# Stereo_Deck.net
KiCad netlist of a schematic drawn in EAGLE
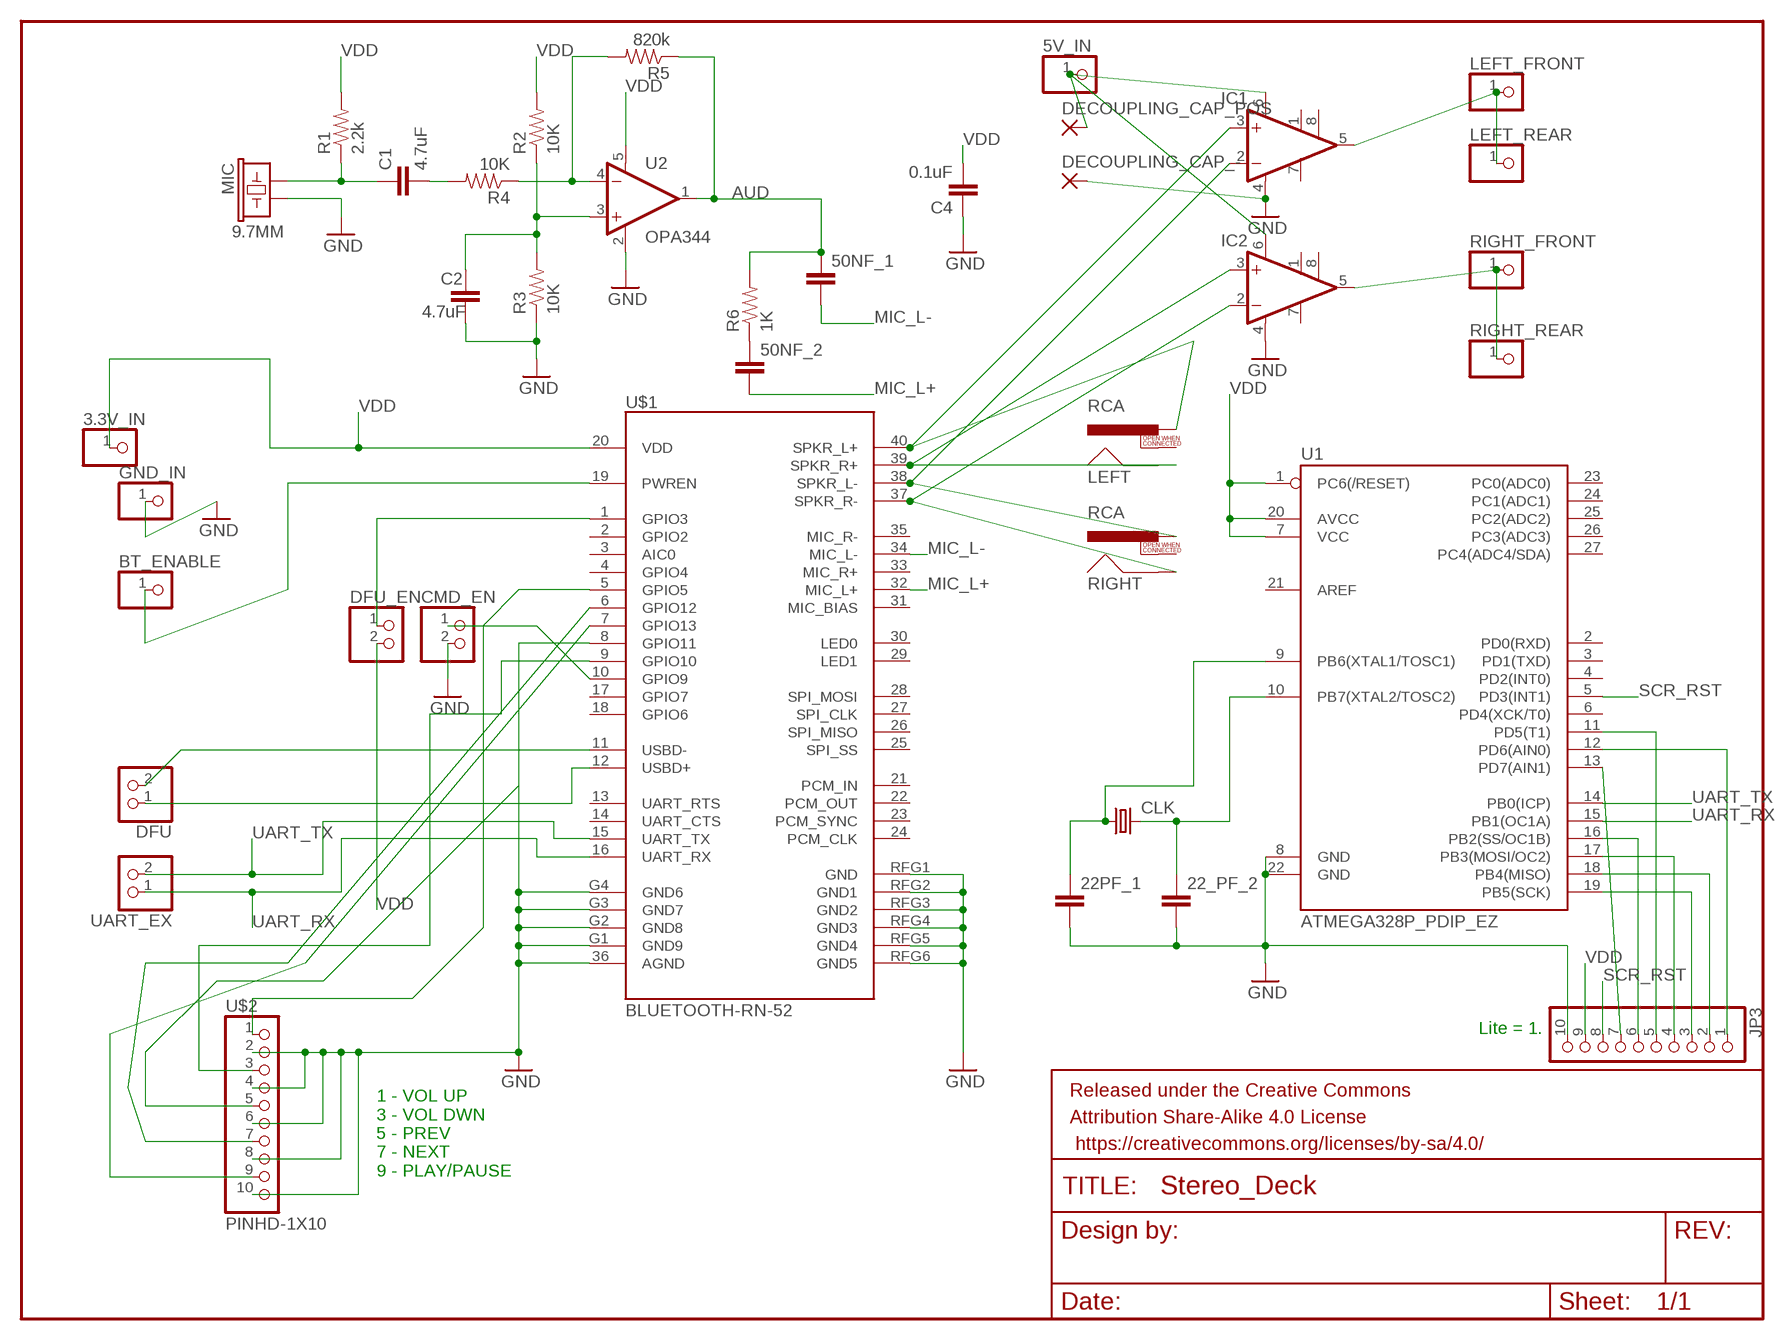
[diagram p0: schematic, sheet 1]

(export (version "E")
  (design (tool "Eeschema 10.0.6"))
  (components
    (comp (ref "3.3V_IN")
      (value "PINHD-1X1")
      (footprint "eagle-import:1X01")
      (libsource (lib "eagle-import") (part "PINHD-1X1"))
    )
    (comp (ref "5V_IN")
      (value "PINHD-1X1")
      (footprint "eagle-import:1X01")
      (libsource (lib "eagle-import") (part "PINHD-1X1"))
    )
    (comp (ref "22PF_1")
      (value "CC0603")
      (footprint "eagle-import:C0603")
      (libsource (lib "eagle-import") (part "CC0603"))
    )
    (comp (ref "22_PF_2")
      (value "CC0603")
      (footprint "eagle-import:C0603")
      (libsource (lib "eagle-import") (part "CC0603"))
    )
    (comp (ref "50NF_1")
      (value "CC0603")
      (footprint "eagle-import:C0603")
      (libsource (lib "eagle-import") (part "CC0603"))
    )
    (comp (ref "50NF_2")
      (value "CC0603")
      (footprint "eagle-import:C0603")
      (libsource (lib "eagle-import") (part "CC0603"))
    )
    (comp (ref "BT_ENABLE")
      (value "PINHD-1X1")
      (footprint "eagle-import:1X01")
      (libsource (lib "eagle-import") (part "PINHD-1X1"))
    )
    (comp (ref "C1")
      (value "4.7uF")
      (footprint "eagle-import:0603-CAP")
      (libsource (lib "eagle-import") (part "4.7UF-6.3V-10%(0603)0603"))
    )
    (comp (ref "C2")
      (value "4.7uF")
      (footprint "eagle-import:0603-CAP")
      (libsource (lib "eagle-import") (part "4.7UF-6.3V-10%(0603)0603"))
    )
    (comp (ref "C4")
      (value "0.1uF")
      (footprint "eagle-import:0603-CAP")
      (libsource (lib "eagle-import") (part "0.1UF-25V(+80/-20%)(0603)"))
    )
    (comp (ref "CLK")
      (value "CRYSTALHC49US")
      (footprint "eagle-import:HC49US")
      (libsource (lib "eagle-import") (part "CRYSTALHC49US"))
    )
    (comp (ref "CMD_EN")
      (value "PINHD-1X2")
      (footprint "eagle-import:1X02")
      (libsource (lib "eagle-import") (part "PINHD-1X2"))
    )
    (comp (ref "DECOUPLING_CAP_-")
      (value "2,15/1,0")
      (footprint "eagle-import:2,15_1,0")
      (libsource (lib "eagle-import") (part "2,15/1,0"))
    )
    (comp (ref "DECOUPLING_CAP_POS")
      (value "2,15/1,0")
      (footprint "eagle-import:2,15_1,0")
      (libsource (lib "eagle-import") (part "2,15/1,0"))
    )
    (comp (ref "DFU")
      (value "PINHD-1X2")
      (footprint "eagle-import:1X02")
      (libsource (lib "eagle-import") (part "PINHD-1X2"))
    )
    (comp (ref "DFU_EN")
      (value "PINHD-1X2")
      (footprint "eagle-import:1X02")
      (libsource (lib "eagle-import") (part "PINHD-1X2"))
    )
    (comp (ref "FRAME1")
      (value "FRAME-LETTER")
      (footprint "eagle-import:CREATIVE_COMMONS")
      (libsource (lib "eagle-import") (part "FRAME-LETTER"))
    )
    (comp (ref "GND_IN")
      (value "PINHD-1X1")
      (footprint "eagle-import:1X01")
      (libsource (lib "eagle-import") (part "PINHD-1X1"))
    )
    (comp (ref "IC1")
      (value "LM386N-1")
      (footprint "eagle-import:DIL08")
      (libsource (lib "eagle-import") (part "LM386?-N1"))
    )
    (comp (ref "IC2")
      (value "LM386N-1")
      (footprint "eagle-import:DIL08")
      (libsource (lib "eagle-import") (part "LM386?-N1"))
    )
    (comp (ref "JP3")
      (value "PINHD-1X10")
      (footprint "eagle-import:1X10")
      (libsource (lib "eagle-import") (part "pinhead_PINHD-1X10"))
    )
    (comp (ref "LEFT")
      (value "RCA")
      (footprint "eagle-import:RCA")
      (libsource (lib "eagle-import") (part "RCA"))
    )
    (comp (ref "LEFT_FRONT")
      (value "PINHD-1X1")
      (footprint "eagle-import:1X01")
      (libsource (lib "eagle-import") (part "PINHD-1X1"))
    )
    (comp (ref "LEFT_REAR")
      (value "PINHD-1X1")
      (footprint "eagle-import:1X01")
      (libsource (lib "eagle-import") (part "PINHD-1X1"))
    )
    (comp (ref "MIC")
      (value "9.7MM")
      (footprint "eagle-import:MIC-9.7MM")
      (libsource (lib "eagle-import") (part "MIC9.7MM"))
    )
    (comp (ref "R1")
      (value "2.2k")
      (footprint "eagle-import:0603-RES")
      (libsource (lib "eagle-import") (part "2.2KOHM-1/10W-1%(0603)"))
    )
    (comp (ref "R2")
      (value "10K")
      (footprint "eagle-import:0603-RES")
      (libsource (lib "eagle-import") (part "10KOHM-1/10W-1%(0603)0603"))
    )
    (comp (ref "R3")
      (value "10K")
      (footprint "eagle-import:0603-RES")
      (libsource (lib "eagle-import") (part "10KOHM-1/10W-1%(0603)0603"))
    )
    (comp (ref "R4")
      (value "10K")
      (footprint "eagle-import:0603-RES")
      (libsource (lib "eagle-import") (part "10KOHM-1/10W-1%(0603)0603"))
    )
    (comp (ref "R5")
      (value "820k")
      (footprint "eagle-import:0603-RES")
      (libsource (lib "eagle-import") (part "820KOHM-1/10W-1%(0603)"))
    )
    (comp (ref "R6")
      (value "1K")
      (footprint "eagle-import:0603-RES")
      (libsource (lib "eagle-import") (part "10KOHM-1/10W-1%(0603)0603"))
    )
    (comp (ref "RIGHT")
      (value "RCA")
      (footprint "eagle-import:RCA")
      (libsource (lib "eagle-import") (part "RCA"))
    )
    (comp (ref "RIGHT_FRONT")
      (value "PINHD-1X1")
      (footprint "eagle-import:1X01")
      (libsource (lib "eagle-import") (part "PINHD-1X1"))
    )
    (comp (ref "RIGHT_REAR")
      (value "PINHD-1X1")
      (footprint "eagle-import:1X01")
      (libsource (lib "eagle-import") (part "PINHD-1X1"))
    )
    (comp (ref "U$1")
      (value "BLUETOOTH-RN-52")
      (footprint "eagle-import:RN-52")
      (libsource (lib "eagle-import") (part "BLUETOOTH-RN-52"))
    )
    (comp (ref "U$2")
      (value "PINHD-1X10")
      (footprint "eagle-import:1X10-BIG")
      (libsource (lib "eagle-import") (part "PINHD-1X10"))
    )
    (comp (ref "U1")
      (value "ATMEGA328P_PDIP_EZ")
      (footprint "eagle-import:DIL28-EZ")
      (libsource (lib "eagle-import") (part "ATMEGA328P_PDIP_EZ"))
    )
    (comp (ref "U2")
      (value "OPA344")
      (footprint "eagle-import:SOT23-5")
      (libsource (lib "eagle-import") (part "OPA344"))
    )
    (comp (ref "UART_EX")
      (value "PINHD-1X2")
      (footprint "eagle-import:1X02")
      (libsource (lib "eagle-import") (part "PINHD-1X2"))
    )
  )
  (nets
    (net (code "1") (name "/AUD") (class "Default")
      (node (ref "50NF_1") (pin "1") (pinfunction "1_1") (pintype "passive"))
      (node (ref "R5") (pin "1") (pinfunction "1_1") (pintype "passive"))
      (node (ref "R6") (pin "2") (pinfunction "2_2") (pintype "passive"))
      (node (ref "U2") (pin "1") (pinfunction "OUT_1") (pintype "output"))
    )
    (net (code "2") (name "/MIC_L+") (class "Default")
      (node (ref "50NF_2") (pin "2") (pinfunction "2_2") (pintype "passive"))
      (node (ref "U$1") (pin "32") (pinfunction "MIC_L+_32") (pintype "bidirectional"))
    )
    (net (code "3") (name "/MIC_L-") (class "Default")
      (node (ref "50NF_1") (pin "2") (pinfunction "2_2") (pintype "passive"))
      (node (ref "U$1") (pin "34") (pinfunction "MIC_L-_34") (pintype "bidirectional"))
    )
    (net (code "4") (name "/SCR_RST") (class "Default")
      (node (ref "JP3") (pin "8") (pinfunction "8_8") (pintype "passive"))
      (node (ref "U1") (pin "5") (pinfunction "PD3(INT1)_5") (pintype "bidirectional"))
    )
    (net (code "5") (name "/UART_RX") (class "Default")
      (node (ref "U$1") (pin "16") (pinfunction "UART_RX_16") (pintype "bidirectional"))
      (node (ref "U1") (pin "15") (pinfunction "PB1(OC1A)_15") (pintype "bidirectional"))
      (node (ref "UART_EX") (pin "1") (pinfunction "1_1") (pintype "passive"))
    )
    (net (code "6") (name "/UART_TX") (class "Default")
      (node (ref "U$1") (pin "15") (pinfunction "UART_TX_15") (pintype "bidirectional"))
      (node (ref "U1") (pin "14") (pinfunction "PB0(ICP)_14") (pintype "bidirectional"))
      (node (ref "UART_EX") (pin "2") (pinfunction "2_2") (pintype "passive"))
    )
    (net (code "7") (name "/VDD") (class "Default")
      (node (ref "3.3V_IN") (pin "1") (pinfunction "1_1") (pintype "passive"))
      (node (ref "C4") (pin "2") (pinfunction "2_2") (pintype "passive"))
      (node (ref "JP3") (pin "9") (pinfunction "9_9") (pintype "passive"))
      (node (ref "R1") (pin "2") (pinfunction "2_2") (pintype "passive"))
      (node (ref "R2") (pin "2") (pinfunction "2_2") (pintype "passive"))
      (node (ref "U$1") (pin "20") (pinfunction "VDD_20") (pintype "bidirectional"))
      (node (ref "U1") (pin "1") (pinfunction "PC6(/RESET)_1") (pintype "bidirectional"))
      (node (ref "U1") (pin "20") (pinfunction "AVCC_20") (pintype "bidirectional"))
      (node (ref "U1") (pin "7") (pinfunction "VCC_7") (pintype "bidirectional"))
      (node (ref "U2") (pin "5") (pinfunction "V+_5") (pintype "power_in"))
    )
    (net (code "8") (name "GND") (class "Default")
      (node (ref "22PF_1") (pin "2") (pinfunction "2_2") (pintype "passive"))
      (node (ref "22_PF_2") (pin "2") (pinfunction "2_2") (pintype "passive"))
      (node (ref "C2") (pin "2") (pinfunction "2_2") (pintype "passive"))
      (node (ref "C4") (pin "1") (pinfunction "1_1") (pintype "passive"))
      (node (ref "CMD_EN") (pin "2") (pinfunction "2_2") (pintype "passive"))
      (node (ref "DECOUPLING_CAP_-") (pin "1") (pinfunction "P_1") (pintype "passive"))
      (node (ref "GND_IN") (pin "1") (pinfunction "1_1") (pintype "passive"))
      (node (ref "IC1") (pin "4") (pinfunction "GND_4") (pintype "power_in"))
      (node (ref "IC2") (pin "4") (pinfunction "GND_4") (pintype "power_in"))
      (node (ref "JP3") (pin "10") (pinfunction "10_10") (pintype "passive"))
      (node (ref "MIC") (pin "2") (pinfunction "2_2") (pintype "passive"))
      (node (ref "R3") (pin "1") (pinfunction "1_1") (pintype "passive"))
      (node (ref "U$1") (pin "36") (pinfunction "AGND_36") (pintype "bidirectional"))
      (node (ref "U$1") (pin "G1") (pinfunction "GND9_G1") (pintype "bidirectional"))
      (node (ref "U$1") (pin "G2") (pinfunction "GND8_G2") (pintype "bidirectional"))
      (node (ref "U$1") (pin "G3") (pinfunction "GND7_G3") (pintype "bidirectional"))
      (node (ref "U$1") (pin "G4") (pinfunction "GND6_G4") (pintype "bidirectional"))
      (node (ref "U$1") (pin "RFG1") (pinfunction "GND_RFG1") (pintype "bidirectional"))
      (node (ref "U$1") (pin "RFG2") (pinfunction "GND1_RFG2") (pintype "bidirectional"))
      (node (ref "U$1") (pin "RFG3") (pinfunction "GND2_RFG3") (pintype "bidirectional"))
      (node (ref "U$1") (pin "RFG4") (pinfunction "GND3_RFG4") (pintype "bidirectional"))
      (node (ref "U$1") (pin "RFG5") (pinfunction "GND4_RFG5") (pintype "bidirectional"))
      (node (ref "U$1") (pin "RFG6") (pinfunction "GND5_RFG6") (pintype "bidirectional"))
      (node (ref "U$2") (pin "10") (pinfunction "10_10") (pintype "passive"))
      (node (ref "U$2") (pin "2") (pinfunction "2_2") (pintype "passive"))
      (node (ref "U$2") (pin "4") (pinfunction "4_4") (pintype "passive"))
      (node (ref "U$2") (pin "6") (pinfunction "6_6") (pintype "passive"))
      (node (ref "U$2") (pin "8") (pinfunction "8_8") (pintype "passive"))
      (node (ref "U1") (pin "22") (pinfunction "GND_22") (pintype "bidirectional"))
      (node (ref "U1") (pin "8") (pinfunction "GND_8") (pintype "bidirectional"))
      (node (ref "U2") (pin "2") (pinfunction "V-_2") (pintype "power_in"))
    )
    (net (code "9") (name "Net-(50NF_2-Pad1)") (class "Default")
      (node (ref "50NF_2") (pin "1") (pinfunction "1_1") (pintype "passive"))
      (node (ref "R6") (pin "1") (pinfunction "1_1") (pintype "passive"))
    )
    (net (code "10") (name "Net-(C1-Pad1)") (class "Default")
      (node (ref "C1") (pin "1") (pinfunction "1_1") (pintype "passive"))
      (node (ref "MIC") (pin "1") (pinfunction "1_1") (pintype "passive"))
      (node (ref "R1") (pin "1") (pinfunction "1_1") (pintype "passive"))
    )
    (net (code "11") (name "Net-(C1-Pad2)") (class "Default")
      (node (ref "C1") (pin "2") (pinfunction "2_2") (pintype "passive"))
      (node (ref "R4") (pin "2") (pinfunction "2_2") (pintype "passive"))
    )
    (net (code "12") (name "Net-(DECOUPLING_CAP_POS-P)") (class "Default")
      (node (ref "5V_IN") (pin "1") (pinfunction "1_1") (pintype "passive"))
      (node (ref "DECOUPLING_CAP_POS") (pin "1") (pinfunction "P_1") (pintype "passive"))
      (node (ref "IC1") (pin "6") (pinfunction "VS_6") (pintype "power_in"))
      (node (ref "IC2") (pin "6") (pinfunction "VS_6") (pintype "power_in"))
    )
    (net (code "13") (name "Net-(IC1-+IN)") (class "Default")
      (node (ref "IC1") (pin "3") (pinfunction "+IN_3") (pintype "input"))
      (node (ref "LEFT") (pin "PIN") (pinfunction "PIN_PIN") (pintype "bidirectional"))
      (node (ref "U$1") (pin "40") (pinfunction "SPKR_L+_40") (pintype "bidirectional"))
    )
    (net (code "14") (name "Net-(IC1--IN)") (class "Default")
      (node (ref "IC1") (pin "2") (pinfunction "-IN_2") (pintype "input"))
      (node (ref "RIGHT") (pin "PIN") (pinfunction "PIN_PIN") (pintype "bidirectional"))
      (node (ref "U$1") (pin "38") (pinfunction "SPKR_L-_38") (pintype "bidirectional"))
    )
    (net (code "15") (name "Net-(IC1-OUT)") (class "Default")
      (node (ref "IC1") (pin "5") (pinfunction "OUT_5") (pintype "output"))
      (node (ref "LEFT_FRONT") (pin "1") (pinfunction "1_1") (pintype "passive"))
      (node (ref "LEFT_REAR") (pin "1") (pinfunction "1_1") (pintype "passive"))
    )
    (net (code "16") (name "Net-(IC2-+IN)") (class "Default")
      (node (ref "IC2") (pin "3") (pinfunction "+IN_3") (pintype "input"))
      (node (ref "LEFT") (pin "SHELL") (pinfunction "SHELL_SHELL") (pintype "bidirectional"))
      (node (ref "U$1") (pin "39") (pinfunction "SPKR_R+_39") (pintype "bidirectional"))
    )
    (net (code "17") (name "Net-(IC2--IN)") (class "Default")
      (node (ref "IC2") (pin "2") (pinfunction "-IN_2") (pintype "input"))
      (node (ref "RIGHT") (pin "SHELL") (pinfunction "SHELL_SHELL") (pintype "bidirectional"))
      (node (ref "U$1") (pin "37") (pinfunction "SPKR_R-_37") (pintype "bidirectional"))
    )
    (net (code "18") (name "Net-(IC2-OUT)") (class "Default")
      (node (ref "IC2") (pin "5") (pinfunction "OUT_5") (pintype "output"))
      (node (ref "RIGHT_FRONT") (pin "1") (pinfunction "1_1") (pintype "passive"))
      (node (ref "RIGHT_REAR") (pin "1") (pinfunction "1_1") (pintype "passive"))
    )
    (net (code "19") (name "Net-(U$1-GPIO3)") (class "Default")
      (node (ref "DFU_EN") (pin "1") (pinfunction "1_1") (pintype "passive"))
      (node (ref "U$1") (pin "1") (pinfunction "GPIO3_1") (pintype "bidirectional"))
    )
    (net (code "20") (name "Net-(U$1-GPIO5)") (class "Default")
      (node (ref "U$1") (pin "5") (pinfunction "GPIO5_5") (pintype "bidirectional"))
      (node (ref "U$2") (pin "1") (pinfunction "1_1") (pintype "passive"))
    )
    (net (code "21") (name "Net-(U$1-GPIO9)") (class "Default")
      (node (ref "CMD_EN") (pin "1") (pinfunction "1_1") (pintype "passive"))
      (node (ref "U$1") (pin "10") (pinfunction "GPIO9_10") (pintype "bidirectional"))
    )
    (net (code "22") (name "Net-(U$1-GPIO10)") (class "Default")
      (node (ref "U$1") (pin "9") (pinfunction "GPIO10_9") (pintype "bidirectional"))
      (node (ref "U$2") (pin "3") (pinfunction "3_3") (pintype "passive"))
    )
    (net (code "23") (name "Net-(U$1-GPIO11)") (class "Default")
      (node (ref "U$1") (pin "8") (pinfunction "GPIO11_8") (pintype "bidirectional"))
      (node (ref "U$2") (pin "5") (pinfunction "5_5") (pintype "passive"))
    )
    (net (code "24") (name "Net-(U$1-GPIO12)") (class "Default")
      (node (ref "U$1") (pin "6") (pinfunction "GPIO12_6") (pintype "bidirectional"))
      (node (ref "U$2") (pin "7") (pinfunction "7_7") (pintype "passive"))
    )
    (net (code "25") (name "Net-(U$1-GPIO13)") (class "Default")
      (node (ref "U$1") (pin "7") (pinfunction "GPIO13_7") (pintype "bidirectional"))
      (node (ref "U$2") (pin "9") (pinfunction "9_9") (pintype "passive"))
    )
    (net (code "26") (name "Net-(U$1-PWREN)") (class "Default")
      (node (ref "BT_ENABLE") (pin "1") (pinfunction "1_1") (pintype "passive"))
      (node (ref "U$1") (pin "19") (pinfunction "PWREN_19") (pintype "bidirectional"))
    )
    (net (code "27") (name "Net-(U$1-USBD+)") (class "Default")
      (node (ref "DFU") (pin "1") (pinfunction "1_1") (pintype "passive"))
      (node (ref "U$1") (pin "12") (pinfunction "USBD+_12") (pintype "bidirectional"))
    )
    (net (code "28") (name "Net-(U$1-USBD-)") (class "Default")
      (node (ref "DFU") (pin "2") (pinfunction "2_2") (pintype "passive"))
      (node (ref "U$1") (pin "11") (pinfunction "USBD-_11") (pintype "bidirectional"))
    )
    (net (code "29") (name "Net-(U1-PB2(SS{slash}OC1B))") (class "Default")
      (node (ref "JP3") (pin "6") (pinfunction "6_6") (pintype "passive"))
      (node (ref "U1") (pin "16") (pinfunction "PB2(SS/OC1B)_16") (pintype "bidirectional"))
    )
    (net (code "30") (name "Net-(U1-PB3(MOSI{slash}OC2))") (class "Default")
      (node (ref "JP3") (pin "4") (pinfunction "4_4") (pintype "passive"))
      (node (ref "U1") (pin "17") (pinfunction "PB3(MOSI/OC2)_17") (pintype "bidirectional"))
    )
    (net (code "31") (name "Net-(U1-PB4(MISO))") (class "Default")
      (node (ref "JP3") (pin "2") (pinfunction "2_2") (pintype "passive"))
      (node (ref "U1") (pin "18") (pinfunction "PB4(MISO)_18") (pintype "bidirectional"))
    )
    (net (code "32") (name "Net-(U1-PB5(SCK))") (class "Default")
      (node (ref "JP3") (pin "3") (pinfunction "3_3") (pintype "passive"))
      (node (ref "U1") (pin "19") (pinfunction "PB5(SCK)_19") (pintype "bidirectional"))
    )
    (net (code "33") (name "Net-(U1-PB6(XTAL1{slash}TOSC1))") (class "Default")
      (node (ref "22PF_1") (pin "1") (pinfunction "1_1") (pintype "passive"))
      (node (ref "CLK") (pin "1") (pinfunction "1_1") (pintype "passive"))
      (node (ref "U1") (pin "9") (pinfunction "PB6(XTAL1/TOSC1)_9") (pintype "bidirectional"))
    )
    (net (code "34") (name "Net-(U1-PB7(XTAL2{slash}TOSC2))") (class "Default")
      (node (ref "22_PF_2") (pin "1") (pinfunction "1_1") (pintype "passive"))
      (node (ref "CLK") (pin "2") (pinfunction "2_2") (pintype "passive"))
      (node (ref "U1") (pin "10") (pinfunction "PB7(XTAL2/TOSC2)_10") (pintype "bidirectional"))
    )
    (net (code "35") (name "Net-(U1-PD5(T1))") (class "Default")
      (node (ref "JP3") (pin "5") (pinfunction "5_5") (pintype "passive"))
      (node (ref "U1") (pin "11") (pinfunction "PD5(T1)_11") (pintype "bidirectional"))
    )
    (net (code "36") (name "Net-(U1-PD6(AIN0))") (class "Default")
      (node (ref "JP3") (pin "1") (pinfunction "1_1") (pintype "passive"))
      (node (ref "U1") (pin "12") (pinfunction "PD6(AIN0)_12") (pintype "bidirectional"))
    )
    (net (code "37") (name "Net-(U1-PD7(AIN1))") (class "Default")
      (node (ref "JP3") (pin "7") (pinfunction "7_7") (pintype "passive"))
      (node (ref "U1") (pin "13") (pinfunction "PD7(AIN1)_13") (pintype "bidirectional"))
    )
    (net (code "38") (name "Net-(U2-+IN)") (class "Default")
      (node (ref "C2") (pin "1") (pinfunction "1_1") (pintype "passive"))
      (node (ref "R2") (pin "1") (pinfunction "1_1") (pintype "passive"))
      (node (ref "R3") (pin "2") (pinfunction "2_2") (pintype "passive"))
      (node (ref "U2") (pin "3") (pinfunction "+IN_3") (pintype "input"))
    )
    (net (code "39") (name "Net-(U2--IN)") (class "Default")
      (node (ref "R4") (pin "1") (pinfunction "1_1") (pintype "passive"))
      (node (ref "R5") (pin "2") (pinfunction "2_2") (pintype "passive"))
      (node (ref "U2") (pin "4") (pinfunction "-IN_4") (pintype "input"))
    )
    (net (code "40") (name "unconnected-(DFU_EN-Pad2)") (class "Default")
      (node (ref "DFU_EN") (pin "2") (pinfunction "2_2") (pintype "passive"))
    )
    (net (code "41") (name "unconnected-(IC1-BYPASS-Pad7)") (class "Default")
      (node (ref "IC1") (pin "7") (pinfunction "BYPASS_7") (pintype "passive"))
    )
    (net (code "42") (name "unconnected-(IC1-GAIN-Pad1)") (class "Default")
      (node (ref "IC1") (pin "1") (pinfunction "GAIN_1") (pintype "passive"))
    )
    (net (code "43") (name "unconnected-(IC1-GAIN-Pad8)") (class "Default")
      (node (ref "IC1") (pin "8") (pinfunction "GAIN_8") (pintype "passive"))
    )
    (net (code "44") (name "unconnected-(IC2-BYPASS-Pad7)") (class "Default")
      (node (ref "IC2") (pin "7") (pinfunction "BYPASS_7") (pintype "passive"))
    )
    (net (code "45") (name "unconnected-(IC2-GAIN-Pad1)") (class "Default")
      (node (ref "IC2") (pin "1") (pinfunction "GAIN_1") (pintype "passive"))
    )
    (net (code "46") (name "unconnected-(IC2-GAIN-Pad8)") (class "Default")
      (node (ref "IC2") (pin "8") (pinfunction "GAIN_8") (pintype "passive"))
    )
    (net (code "47") (name "unconnected-(LEFT-PadSWITCH)") (class "Default")
      (node (ref "LEFT") (pin "SWITCH") (pinfunction "SWITCH_SWITCH") (pintype "bidirectional"))
    )
    (net (code "48") (name "unconnected-(RIGHT-PadSWITCH)") (class "Default")
      (node (ref "RIGHT") (pin "SWITCH") (pinfunction "SWITCH_SWITCH") (pintype "bidirectional"))
    )
    (net (code "49") (name "unconnected-(U$1-AIC0-Pad3)") (class "Default")
      (node (ref "U$1") (pin "3") (pinfunction "AIC0_3") (pintype "bidirectional"))
    )
    (net (code "50") (name "unconnected-(U$1-GPIO2-Pad2)") (class "Default")
      (node (ref "U$1") (pin "2") (pinfunction "GPIO2_2") (pintype "bidirectional"))
    )
    (net (code "51") (name "unconnected-(U$1-GPIO4-Pad4)") (class "Default")
      (node (ref "U$1") (pin "4") (pinfunction "GPIO4_4") (pintype "bidirectional"))
    )
    (net (code "52") (name "unconnected-(U$1-GPIO6-Pad18)") (class "Default")
      (node (ref "U$1") (pin "18") (pinfunction "GPIO6_18") (pintype "bidirectional"))
    )
    (net (code "53") (name "unconnected-(U$1-GPIO7-Pad17)") (class "Default")
      (node (ref "U$1") (pin "17") (pinfunction "GPIO7_17") (pintype "bidirectional"))
    )
    (net (code "54") (name "unconnected-(U$1-LED0-Pad30)") (class "Default")
      (node (ref "U$1") (pin "30") (pinfunction "LED0_30") (pintype "bidirectional"))
    )
    (net (code "55") (name "unconnected-(U$1-LED1-Pad29)") (class "Default")
      (node (ref "U$1") (pin "29") (pinfunction "LED1_29") (pintype "bidirectional"))
    )
    (net (code "56") (name "unconnected-(U$1-MIC_BIAS-Pad31)") (class "Default")
      (node (ref "U$1") (pin "31") (pinfunction "MIC_BIAS_31") (pintype "bidirectional"))
    )
    (net (code "57") (name "unconnected-(U$1-MIC_R+-Pad33)") (class "Default")
      (node (ref "U$1") (pin "33") (pinfunction "MIC_R+_33") (pintype "bidirectional"))
    )
    (net (code "58") (name "unconnected-(U$1-MIC_R--Pad35)") (class "Default")
      (node (ref "U$1") (pin "35") (pinfunction "MIC_R-_35") (pintype "bidirectional"))
    )
    (net (code "59") (name "unconnected-(U$1-PCM_CLK-Pad24)") (class "Default")
      (node (ref "U$1") (pin "24") (pinfunction "PCM_CLK_24") (pintype "bidirectional"))
    )
    (net (code "60") (name "unconnected-(U$1-PCM_IN-Pad21)") (class "Default")
      (node (ref "U$1") (pin "21") (pinfunction "PCM_IN_21") (pintype "bidirectional"))
    )
    (net (code "61") (name "unconnected-(U$1-PCM_OUT-Pad22)") (class "Default")
      (node (ref "U$1") (pin "22") (pinfunction "PCM_OUT_22") (pintype "bidirectional"))
    )
    (net (code "62") (name "unconnected-(U$1-PCM_SYNC-Pad23)") (class "Default")
      (node (ref "U$1") (pin "23") (pinfunction "PCM_SYNC_23") (pintype "bidirectional"))
    )
    (net (code "63") (name "unconnected-(U$1-SPI_CLK-Pad27)") (class "Default")
      (node (ref "U$1") (pin "27") (pinfunction "SPI_CLK_27") (pintype "bidirectional"))
    )
    (net (code "64") (name "unconnected-(U$1-SPI_MISO-Pad26)") (class "Default")
      (node (ref "U$1") (pin "26") (pinfunction "SPI_MISO_26") (pintype "bidirectional"))
    )
    (net (code "65") (name "unconnected-(U$1-SPI_MOSI-Pad28)") (class "Default")
      (node (ref "U$1") (pin "28") (pinfunction "SPI_MOSI_28") (pintype "bidirectional"))
    )
    (net (code "66") (name "unconnected-(U$1-SPI_SS-Pad25)") (class "Default")
      (node (ref "U$1") (pin "25") (pinfunction "SPI_SS_25") (pintype "bidirectional"))
    )
    (net (code "67") (name "unconnected-(U$1-UART_CTS-Pad14)") (class "Default")
      (node (ref "U$1") (pin "14") (pinfunction "UART_CTS_14") (pintype "bidirectional"))
    )
    (net (code "68") (name "unconnected-(U$1-UART_RTS-Pad13)") (class "Default")
      (node (ref "U$1") (pin "13") (pinfunction "UART_RTS_13") (pintype "bidirectional"))
    )
    (net (code "69") (name "unconnected-(U1-AREF-Pad21)") (class "Default")
      (node (ref "U1") (pin "21") (pinfunction "AREF_21") (pintype "bidirectional"))
    )
    (net (code "70") (name "unconnected-(U1-PC0(ADC0)-Pad23)") (class "Default")
      (node (ref "U1") (pin "23") (pinfunction "PC0(ADC0)_23") (pintype "bidirectional"))
    )
    (net (code "71") (name "unconnected-(U1-PC1(ADC1)-Pad24)") (class "Default")
      (node (ref "U1") (pin "24") (pinfunction "PC1(ADC1)_24") (pintype "bidirectional"))
    )
    (net (code "72") (name "unconnected-(U1-PC2(ADC2)-Pad25)") (class "Default")
      (node (ref "U1") (pin "25") (pinfunction "PC2(ADC2)_25") (pintype "bidirectional"))
    )
    (net (code "73") (name "unconnected-(U1-PC3(ADC3)-Pad26)") (class "Default")
      (node (ref "U1") (pin "26") (pinfunction "PC3(ADC3)_26") (pintype "bidirectional"))
    )
    (net (code "74") (name "unconnected-(U1-PC4(ADC4{slash}SDA)-Pad27)") (class "Default")
      (node (ref "U1") (pin "27") (pinfunction "PC4(ADC4/SDA)_27") (pintype "bidirectional"))
    )
    (net (code "75") (name "unconnected-(U1-PD0(RXD)-Pad2)") (class "Default")
      (node (ref "U1") (pin "2") (pinfunction "PD0(RXD)_2") (pintype "bidirectional"))
    )
    (net (code "76") (name "unconnected-(U1-PD1(TXD)-Pad3)") (class "Default")
      (node (ref "U1") (pin "3") (pinfunction "PD1(TXD)_3") (pintype "bidirectional"))
    )
    (net (code "77") (name "unconnected-(U1-PD2(INT0)-Pad4)") (class "Default")
      (node (ref "U1") (pin "4") (pinfunction "PD2(INT0)_4") (pintype "bidirectional"))
    )
    (net (code "78") (name "unconnected-(U1-PD4(XCK{slash}T0)-Pad6)") (class "Default")
      (node (ref "U1") (pin "6") (pinfunction "PD4(XCK/T0)_6") (pintype "bidirectional"))
    )
  )
)
